# TSAL_Proto18.net
KiCad netlist of a schematic drawn in EAGLE
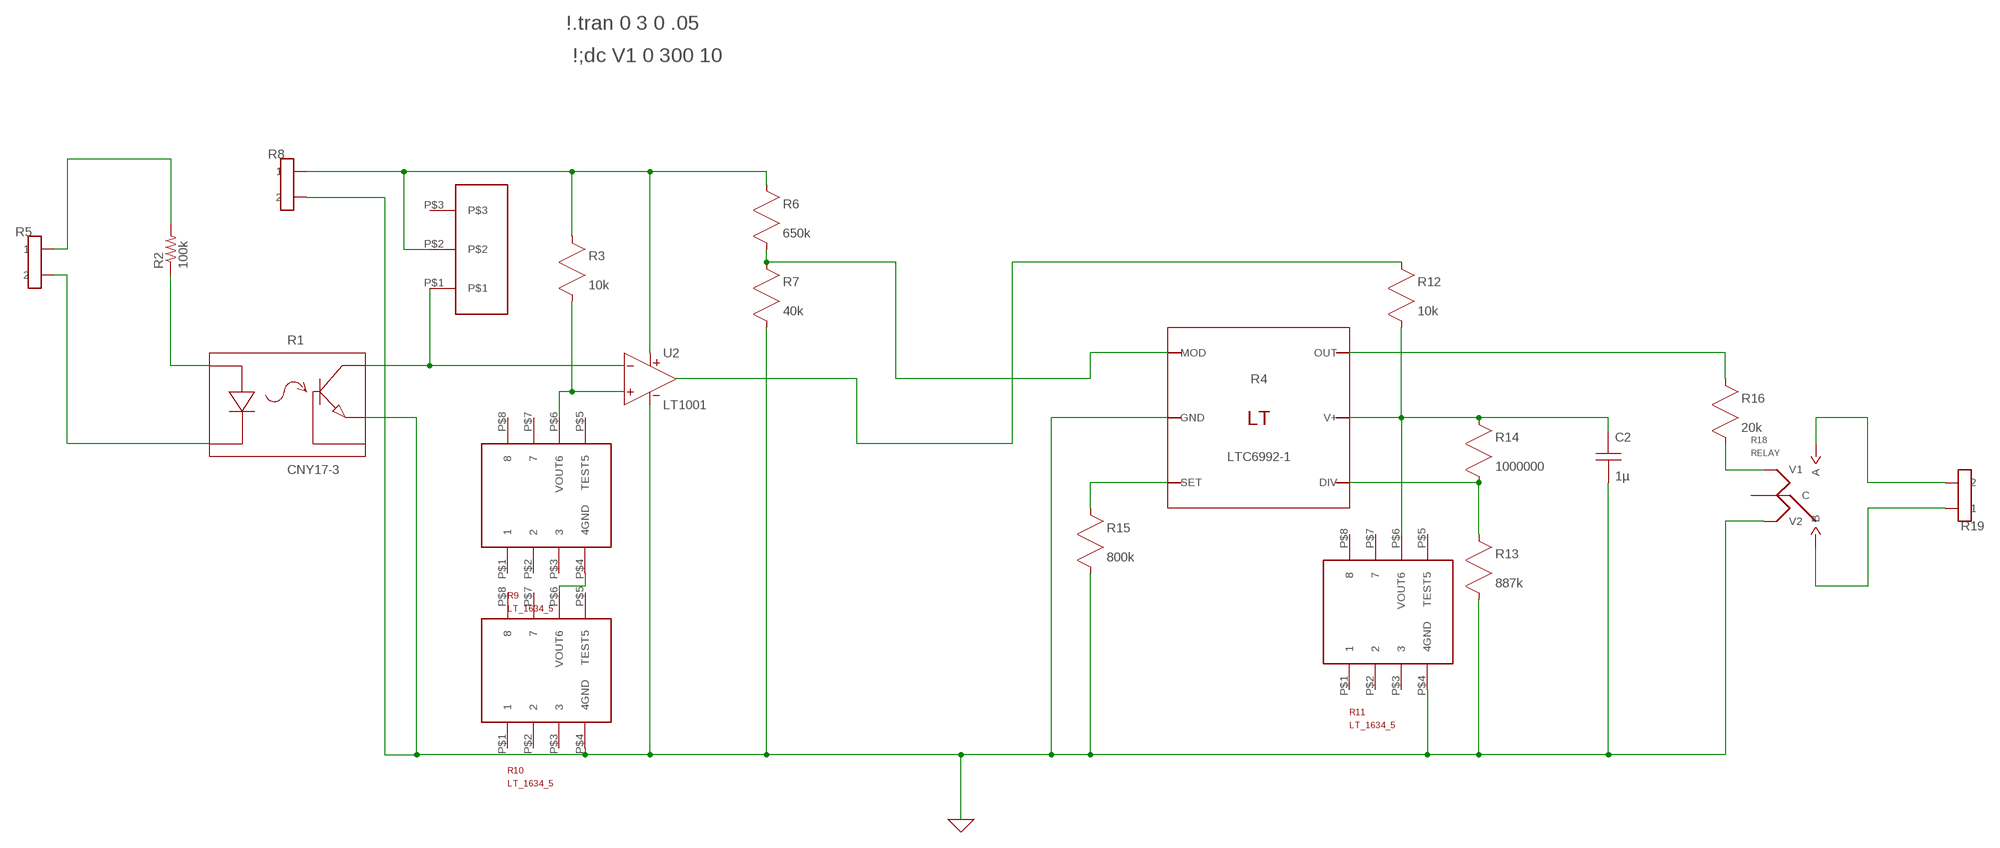
[diagram p0: schematic, sheet 1]

(export (version "E")
  (design (tool "Eeschema 10.0.6"))
  (components
    (comp (ref "C2")
      (value "1µ")
      (footprint "eagle-import:C0805")
      (libsource (lib "eagle-import") (part "CAP"))
    )
    (comp (ref "R1")
      (value "CNY17-3")
      (footprint "eagle-import:CNY17-3")
      (libsource (lib "eagle-import") (part "CNY17-3"))
    )
    (comp (ref "R2")
      (value "100k")
      (footprint "eagle-import:P0817_22")
      (libsource (lib "eagle-import") (part "R-US_0817/22"))
    )
    (comp (ref "R3")
      (value "10k")
      (footprint "eagle-import:R0805")
      (libsource (lib "eagle-import") (part "RES"))
    )
    (comp (ref "R4")
      (value "LTC6992-1")
      (footprint "eagle-import:LTC6992-1")
      (libsource (lib "eagle-import") (part "LTC6992-1"))
    )
    (comp (ref "R5")
      (value "CONN_2")
      (footprint "eagle-import:CONNECTOR_2")
      (libsource (lib "eagle-import") (part "CONN_2"))
    )
    (comp (ref "R6")
      (value "650k")
      (footprint "eagle-import:R0805")
      (libsource (lib "eagle-import") (part "RES"))
    )
    (comp (ref "R7")
      (value "40k")
      (footprint "eagle-import:R0805")
      (libsource (lib "eagle-import") (part "RES"))
    )
    (comp (ref "R8")
      (value "CONN_2")
      (footprint "eagle-import:CONNECTOR_2")
      (libsource (lib "eagle-import") (part "CONN_2"))
    )
    (comp (ref "R9")
      (value "LT_1634_5MS8")
      (footprint "eagle-import:LT_1634_5")
      (libsource (lib "eagle-import") (part "LT_1634_5MS8"))
    )
    (comp (ref "R10")
      (value "LT_1634_5MS8")
      (footprint "eagle-import:LT_1634_5")
      (libsource (lib "eagle-import") (part "LT_1634_5MS8"))
    )
    (comp (ref "R11")
      (value "LT_1634_5MS8")
      (footprint "eagle-import:LT_1634_5")
      (libsource (lib "eagle-import") (part "LT_1634_5MS8"))
    )
    (comp (ref "R12")
      (value "10k")
      (footprint "eagle-import:R0805")
      (libsource (lib "eagle-import") (part "RES"))
    )
    (comp (ref "R13")
      (value "887k")
      (footprint "eagle-import:R0805")
      (libsource (lib "eagle-import") (part "RES"))
    )
    (comp (ref "R14")
      (value "1000000")
      (footprint "eagle-import:R0805")
      (libsource (lib "eagle-import") (part "RES"))
    )
    (comp (ref "R15")
      (value "800k")
      (footprint "eagle-import:R0805")
      (libsource (lib "eagle-import") (part "RES"))
    )
    (comp (ref "R16")
      (value "20k")
      (footprint "eagle-import:R0805")
      (libsource (lib "eagle-import") (part "RES"))
    )
    (comp (ref "R17")
      (value "RK097111T")
      (footprint "eagle-import:RK097111T")
      (libsource (lib "eagle-import") (part "RK097111T"))
    )
    (comp (ref "R18")
      (value "RELAY")
      (footprint "eagle-import:RELAY")
      (libsource (lib "eagle-import") (part "RELAY"))
    )
    (comp (ref "R19")
      (value "CONN_2")
      (footprint "eagle-import:CONNECTOR_2")
      (libsource (lib "eagle-import") (part "CONN_2"))
    )
    (comp (ref "U2")
      (value "LT1001")
      (footprint "eagle-import:S8")
      (libsource (lib "eagle-import") (part "LT1001"))
    )
  )
  (nets
    (net (code "1") (name "0") (class "Default")
      (node (ref "C2") (pin "2") (pinfunction "B_2") (pintype "passive"))
      (node (ref "R1") (pin "P$4") (pinfunction "E_P$4") (pintype "passive"))
      (node (ref "R10") (pin "P$4") (pinfunction "4GND_P$4") (pintype "bidirectional"))
      (node (ref "R11") (pin "P$4") (pinfunction "4GND_P$4") (pintype "bidirectional"))
      (node (ref "R13") (pin "2") (pinfunction "B_2") (pintype "passive"))
      (node (ref "R15") (pin "2") (pinfunction "B_2") (pintype "passive"))
      (node (ref "R18") (pin "V2") (pinfunction "V2_V2") (pintype "bidirectional"))
      (node (ref "R4") (pin "P$2") (pinfunction "GND_P$2") (pintype "passive"))
      (node (ref "R7") (pin "2") (pinfunction "B_2") (pintype "passive"))
      (node (ref "R8") (pin "3") (pinfunction "2_3") (pintype "bidirectional"))
      (node (ref "R8") (pin "4") (pinfunction "2_4") (pintype "bidirectional"))
      (node (ref "U2") (pin "4") (pinfunction "V-_4") (pintype "passive"))
    )
    (net (code "2") (name "Net-(C2-A)") (class "Default")
      (node (ref "C2") (pin "1") (pinfunction "A_1") (pintype "passive"))
      (node (ref "R11") (pin "P$6") (pinfunction "VOUT6_P$6") (pintype "bidirectional"))
      (node (ref "R12") (pin "2") (pinfunction "B_2") (pintype "passive"))
      (node (ref "R14") (pin "1") (pinfunction "A_1") (pintype "passive"))
      (node (ref "R4") (pin "P$5") (pinfunction "V+_P$5") (pintype "passive"))
    )
    (net (code "3") (name "Net-(R1-A)") (class "Default")
      (node (ref "R1") (pin "P$1") (pinfunction "A_P$1") (pintype "passive"))
      (node (ref "R2") (pin "1") (pinfunction "1_1") (pintype "passive"))
    )
    (net (code "4") (name "Net-(R1-C)") (class "Default")
      (node (ref "R1") (pin "P$5") (pinfunction "C_P$5") (pintype "passive"))
      (node (ref "R17") (pin "P$1") (pinfunction "P$1_P$1") (pintype "bidirectional"))
      (node (ref "U2") (pin "2") (pinfunction "IN-_2") (pintype "passive"))
    )
    (net (code "5") (name "Net-(R1-K)") (class "Default")
      (node (ref "R1") (pin "P$2") (pinfunction "K_P$2") (pintype "passive"))
      (node (ref "R5") (pin "3") (pinfunction "2_3") (pintype "bidirectional"))
      (node (ref "R5") (pin "4") (pinfunction "2_4") (pintype "bidirectional"))
    )
    (net (code "6") (name "Net-(R2-Pad2)") (class "Default")
      (node (ref "R2") (pin "2") (pinfunction "2_2") (pintype "passive"))
      (node (ref "R5") (pin "1") (pinfunction "1_1") (pintype "bidirectional"))
      (node (ref "R5") (pin "2") (pinfunction "1_2") (pintype "bidirectional"))
    )
    (net (code "7") (name "Net-(R3-A)") (class "Default")
      (node (ref "R17") (pin "P$2") (pinfunction "P$2_P$2") (pintype "bidirectional"))
      (node (ref "R3") (pin "1") (pinfunction "A_1") (pintype "passive"))
      (node (ref "R6") (pin "1") (pinfunction "A_1") (pintype "passive"))
      (node (ref "R8") (pin "1") (pinfunction "1_1") (pintype "bidirectional"))
      (node (ref "R8") (pin "2") (pinfunction "1_2") (pintype "bidirectional"))
      (node (ref "U2") (pin "8") (pinfunction "V+_8") (pintype "passive"))
    )
    (net (code "8") (name "Net-(R3-B)") (class "Default")
      (node (ref "R3") (pin "2") (pinfunction "B_2") (pintype "passive"))
      (node (ref "R9") (pin "P$6") (pinfunction "VOUT6_P$6") (pintype "bidirectional"))
      (node (ref "U2") (pin "1") (pinfunction "IN+_1") (pintype "passive"))
    )
    (net (code "9") (name "Net-(R4-MOD)") (class "Default")
      (node (ref "R4") (pin "P$1") (pinfunction "MOD_P$1") (pintype "passive"))
      (node (ref "R6") (pin "2") (pinfunction "B_2") (pintype "passive"))
      (node (ref "R7") (pin "1") (pinfunction "A_1") (pintype "passive"))
    )
    (net (code "10") (name "Net-(R10-VOUT6)") (class "Default")
      (node (ref "R10") (pin "P$6") (pinfunction "VOUT6_P$6") (pintype "bidirectional"))
      (node (ref "R9") (pin "P$4") (pinfunction "4GND_P$4") (pintype "bidirectional"))
    )
    (net (code "11") (name "Net-(R12-A)") (class "Default")
      (node (ref "R12") (pin "1") (pinfunction "A_1") (pintype "passive"))
      (node (ref "U2") (pin "3") (pinfunction "OUT_3") (pintype "passive"))
    )
    (net (code "12") (name "Net-(R13-A)") (class "Default")
      (node (ref "R13") (pin "1") (pinfunction "A_1") (pintype "passive"))
      (node (ref "R14") (pin "2") (pinfunction "B_2") (pintype "passive"))
      (node (ref "R4") (pin "P$4") (pinfunction "DIV_P$4") (pintype "passive"))
    )
    (net (code "13") (name "Net-(R15-A)") (class "Default")
      (node (ref "R15") (pin "1") (pinfunction "A_1") (pintype "passive"))
      (node (ref "R4") (pin "P$3") (pinfunction "SET_P$3") (pintype "passive"))
    )
    (net (code "14") (name "Net-(R16-A)") (class "Default")
      (node (ref "R16") (pin "1") (pinfunction "A_1") (pintype "passive"))
      (node (ref "R4") (pin "P$6") (pinfunction "OUT_P$6") (pintype "passive"))
    )
    (net (code "15") (name "Net-(R16-B)") (class "Default")
      (node (ref "R16") (pin "2") (pinfunction "B_2") (pintype "passive"))
      (node (ref "R18") (pin "V1") (pinfunction "V1_V1") (pintype "bidirectional"))
    )
    (net (code "16") (name "Net-(R18-PadA)") (class "Default")
      (node (ref "R18") (pin "A") (pinfunction "A_A") (pintype "bidirectional"))
      (node (ref "R19") (pin "3") (pinfunction "2_3") (pintype "bidirectional"))
      (node (ref "R19") (pin "4") (pinfunction "2_4") (pintype "bidirectional"))
    )
    (net (code "17") (name "Net-(R18-PadB)") (class "Default")
      (node (ref "R18") (pin "B") (pinfunction "B_B") (pintype "bidirectional"))
      (node (ref "R19") (pin "1") (pinfunction "1_1") (pintype "bidirectional"))
      (node (ref "R19") (pin "2") (pinfunction "1_2") (pintype "bidirectional"))
    )
    (net (code "18") (name "unconnected-(R1-B-PadP$6)") (class "Default")
      (node (ref "R1") (pin "P$6") (pinfunction "B_P$6") (pintype "passive"))
    )
    (net (code "19") (name "unconnected-(R9-1-PadP$1)") (class "Default")
      (node (ref "R9") (pin "P$1") (pinfunction "1_P$1") (pintype "bidirectional"))
    )
    (net (code "20") (name "unconnected-(R9-2-PadP$2)") (class "Default")
      (node (ref "R9") (pin "P$2") (pinfunction "2_P$2") (pintype "bidirectional"))
    )
    (net (code "21") (name "unconnected-(R9-3-PadP$3)") (class "Default")
      (node (ref "R9") (pin "P$3") (pinfunction "3_P$3") (pintype "bidirectional"))
    )
    (net (code "22") (name "unconnected-(R9-7-PadP$7)") (class "Default")
      (node (ref "R9") (pin "P$7") (pinfunction "7_P$7") (pintype "bidirectional"))
    )
    (net (code "23") (name "unconnected-(R9-8-PadP$8)") (class "Default")
      (node (ref "R9") (pin "P$8") (pinfunction "8_P$8") (pintype "bidirectional"))
    )
    (net (code "24") (name "unconnected-(R9-TEST5-PadP$5)") (class "Default")
      (node (ref "R9") (pin "P$5") (pinfunction "TEST5_P$5") (pintype "bidirectional"))
    )
    (net (code "25") (name "unconnected-(R10-1-PadP$1)") (class "Default")
      (node (ref "R10") (pin "P$1") (pinfunction "1_P$1") (pintype "bidirectional"))
    )
    (net (code "26") (name "unconnected-(R10-2-PadP$2)") (class "Default")
      (node (ref "R10") (pin "P$2") (pinfunction "2_P$2") (pintype "bidirectional"))
    )
    (net (code "27") (name "unconnected-(R10-3-PadP$3)") (class "Default")
      (node (ref "R10") (pin "P$3") (pinfunction "3_P$3") (pintype "bidirectional"))
    )
    (net (code "28") (name "unconnected-(R10-7-PadP$7)") (class "Default")
      (node (ref "R10") (pin "P$7") (pinfunction "7_P$7") (pintype "bidirectional"))
    )
    (net (code "29") (name "unconnected-(R10-8-PadP$8)") (class "Default")
      (node (ref "R10") (pin "P$8") (pinfunction "8_P$8") (pintype "bidirectional"))
    )
    (net (code "30") (name "unconnected-(R10-TEST5-PadP$5)") (class "Default")
      (node (ref "R10") (pin "P$5") (pinfunction "TEST5_P$5") (pintype "bidirectional"))
    )
    (net (code "31") (name "unconnected-(R11-1-PadP$1)") (class "Default")
      (node (ref "R11") (pin "P$1") (pinfunction "1_P$1") (pintype "bidirectional"))
    )
    (net (code "32") (name "unconnected-(R11-2-PadP$2)") (class "Default")
      (node (ref "R11") (pin "P$2") (pinfunction "2_P$2") (pintype "bidirectional"))
    )
    (net (code "33") (name "unconnected-(R11-3-PadP$3)") (class "Default")
      (node (ref "R11") (pin "P$3") (pinfunction "3_P$3") (pintype "bidirectional"))
    )
    (net (code "34") (name "unconnected-(R11-7-PadP$7)") (class "Default")
      (node (ref "R11") (pin "P$7") (pinfunction "7_P$7") (pintype "bidirectional"))
    )
    (net (code "35") (name "unconnected-(R11-8-PadP$8)") (class "Default")
      (node (ref "R11") (pin "P$8") (pinfunction "8_P$8") (pintype "bidirectional"))
    )
    (net (code "36") (name "unconnected-(R11-TEST5-PadP$5)") (class "Default")
      (node (ref "R11") (pin "P$5") (pinfunction "TEST5_P$5") (pintype "bidirectional"))
    )
    (net (code "37") (name "unconnected-(R17-PadP$3)") (class "Default")
      (node (ref "R17") (pin "P$3") (pinfunction "P$3_P$3") (pintype "bidirectional"))
    )
    (net (code "38") (name "unconnected-(R18-C-PadCENTER)") (class "Default")
      (node (ref "R18") (pin "CENTER") (pinfunction "C_CENTER") (pintype "bidirectional"))
    )
  )
)
